# NCKH_cap_truong_Thien.net
KiCad netlist of a schematic drawn in Altium Designer
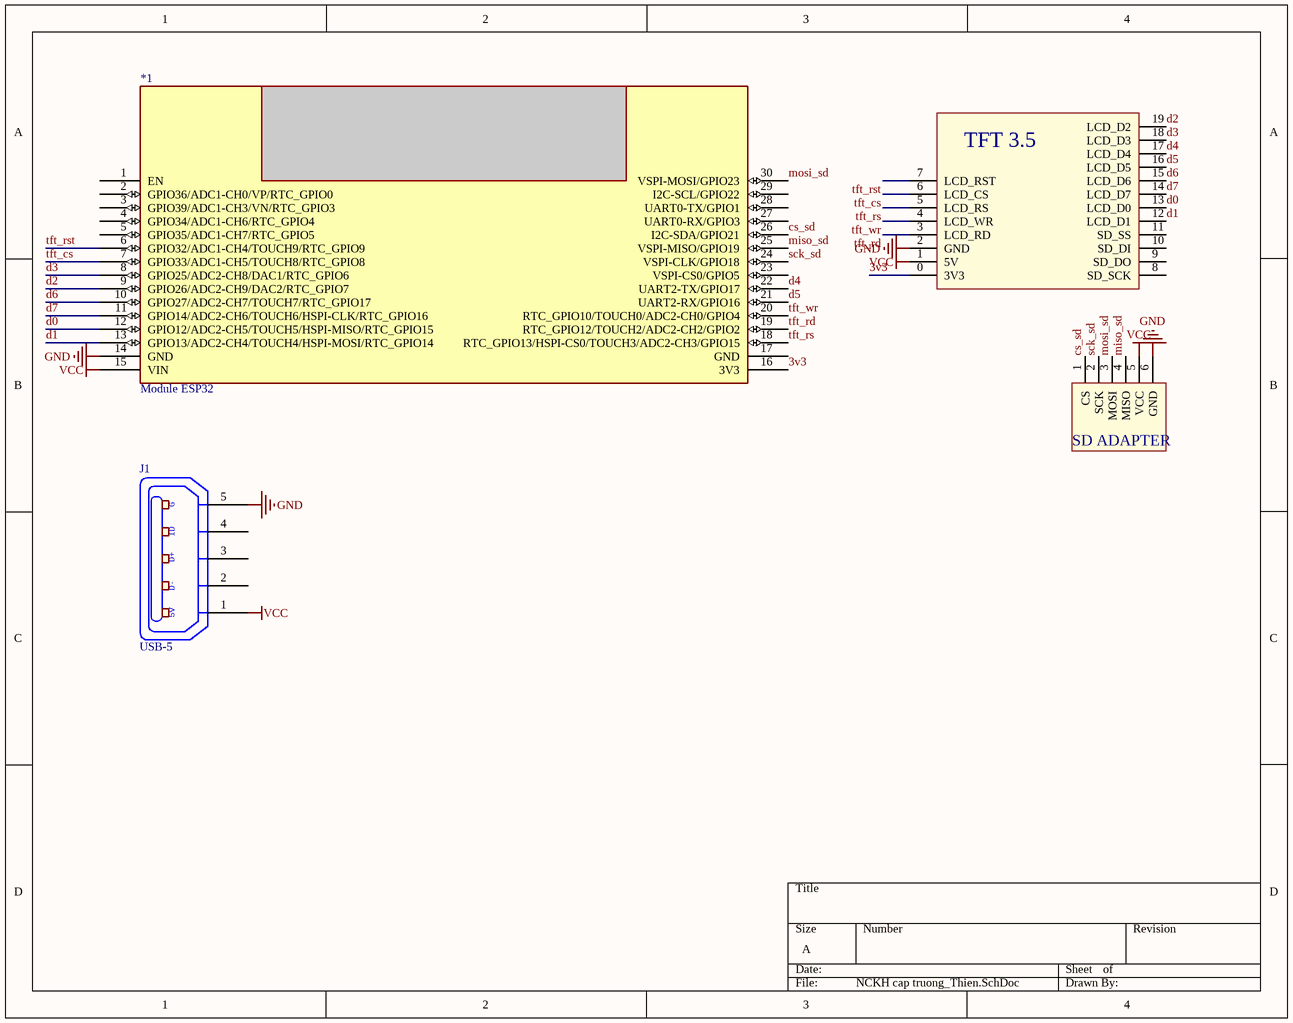
[diagram p0: NCKH cap truong_Thien.SchDoc]

(export (version "E")
  (design (tool "Eeschema 10.0.6"))
  (components
    (comp (ref "*1")
      (value "Module ESP32")
      (footprint "Module ESP32")
      (libsource (lib "Lib_NTD") (part "Module ESP32"))
    )
    (comp (ref "*2")
      (value "LCD TFT 3.5 Shield")
      (footprint "LCD TFT 3.5 Shield")
      (libsource (lib "Lib_NTD") (part "LCD TFT 3.5 Shield"))
    )
    (comp (ref "*3")
      (value "Module MicroSD Adapter")
      (footprint "Module MicroSD Adapter")
      (libsource (lib "Lib_NTD") (part "Module MicroSD Adapter"))
    )
    (comp (ref "J1")
      (value "USB-5")
      (footprint "USB-M1")
      (fields
        (field (name "MANUFACTURER") "FCI")
        (field (name "MANUFACTURER PART NUMBER") "10118193-0001LF")
        (field (name ".CREATOR") "MM")
        (field (name ".CHECKED PCB") "RF")
        (field (name ".CHECKED SCH") "MM")
      )
      (libsource (lib "LIBRARY") (part "USB-5"))
    )
  )
  (nets
    (net (code "1") (name "/3v3") (class "Default")
      (node (ref "*1") (pin "16") (pinfunction "3V3_16") (pintype "power_in"))
      (node (ref "*2") (pin "0") (pinfunction "3V3_0") (pintype "passive"))
    )
    (net (code "2") (name "/cs_sd") (class "Default")
      (node (ref "*1") (pin "26") (pinfunction "I2C-SDA/GPIO21_26") (pintype "bidirectional"))
      (node (ref "*3") (pin "1") (pinfunction "CS_1") (pintype "passive"))
    )
    (net (code "3") (name "/d0") (class "Default")
      (node (ref "*1") (pin "12") (pinfunction "GPIO12/ADC2-CH5/TOUCH5/HSPI-MISO/RTC_GPIO15_12") (pintype "bidirectional"))
      (node (ref "*2") (pin "13") (pinfunction "LCD_D0_13") (pintype "passive"))
    )
    (net (code "4") (name "/d1") (class "Default")
      (node (ref "*1") (pin "13") (pinfunction "GPIO13/ADC2-CH4/TOUCH4/HSPI-MOSI/RTC_GPIO14_13") (pintype "bidirectional"))
      (node (ref "*2") (pin "12") (pinfunction "LCD_D1_12") (pintype "passive"))
    )
    (net (code "5") (name "/d2") (class "Default")
      (node (ref "*1") (pin "9") (pinfunction "GPIO26/ADC2-CH9/DAC2/RTC_GPIO7_9") (pintype "bidirectional"))
      (node (ref "*2") (pin "19") (pinfunction "LCD_D2_19") (pintype "passive"))
    )
    (net (code "6") (name "/d3") (class "Default")
      (node (ref "*1") (pin "8") (pinfunction "GPIO25/ADC2-CH8/DAC1/RTC_GPIO6_8") (pintype "bidirectional"))
      (node (ref "*2") (pin "18") (pinfunction "LCD_D3_18") (pintype "passive"))
    )
    (net (code "7") (name "/d4") (class "Default")
      (node (ref "*1") (pin "22") (pinfunction "UART2-TX/GPIO17_22") (pintype "bidirectional"))
      (node (ref "*2") (pin "17") (pinfunction "LCD_D4_17") (pintype "passive"))
    )
    (net (code "8") (name "/d5") (class "Default")
      (node (ref "*1") (pin "21") (pinfunction "UART2-RX/GPIO16_21") (pintype "bidirectional"))
      (node (ref "*2") (pin "16") (pinfunction "LCD_D5_16") (pintype "passive"))
    )
    (net (code "9") (name "/d6") (class "Default")
      (node (ref "*1") (pin "10") (pinfunction "GPIO27/ADC2-CH7/TOUCH7/RTC_GPIO17_10") (pintype "bidirectional"))
      (node (ref "*2") (pin "15") (pinfunction "LCD_D6_15") (pintype "passive"))
    )
    (net (code "10") (name "/d7") (class "Default")
      (node (ref "*1") (pin "11") (pinfunction "GPIO14/ADC2-CH6/TOUCH6/HSPI-CLK/RTC_GPIO16_11") (pintype "bidirectional"))
      (node (ref "*2") (pin "14") (pinfunction "LCD_D7_14") (pintype "passive"))
    )
    (net (code "11") (name "/miso_sd") (class "Default")
      (node (ref "*1") (pin "25") (pinfunction "VSPI-MISO/GPIO19_25") (pintype "bidirectional"))
      (node (ref "*3") (pin "4") (pinfunction "MISO_4") (pintype "passive"))
    )
    (net (code "12") (name "/mosi_sd") (class "Default")
      (node (ref "*1") (pin "30") (pinfunction "VSPI-MOSI/GPIO23_30") (pintype "bidirectional"))
      (node (ref "*3") (pin "3") (pinfunction "MOSI_3") (pintype "passive"))
    )
    (net (code "13") (name "/sck_sd") (class "Default")
      (node (ref "*1") (pin "24") (pinfunction "VSPI-CLK/GPIO18_24") (pintype "bidirectional"))
      (node (ref "*3") (pin "2") (pinfunction "SCK_2") (pintype "passive"))
    )
    (net (code "14") (name "/tft_cs") (class "Default")
      (node (ref "*1") (pin "7") (pinfunction "GPIO33/ADC1-CH5/TOUCH8/RTC_GPIO8_7") (pintype "bidirectional"))
      (node (ref "*2") (pin "6") (pinfunction "LCD_CS_6") (pintype "passive"))
    )
    (net (code "15") (name "/tft_rd") (class "Default")
      (node (ref "*1") (pin "19") (pinfunction "RTC_GPIO12/TOUCH2/ADC2-CH2/GPIO2_19") (pintype "bidirectional"))
      (node (ref "*2") (pin "3") (pinfunction "LCD_RD_3") (pintype "passive"))
    )
    (net (code "16") (name "/tft_rs") (class "Default")
      (node (ref "*1") (pin "18") (pinfunction "RTC_GPIO13/HSPI-CS0/TOUCH3/ADC2-CH3/GPIO15_18") (pintype "bidirectional"))
      (node (ref "*2") (pin "5") (pinfunction "LCD_RS_5") (pintype "passive"))
    )
    (net (code "17") (name "/tft_rst") (class "Default")
      (node (ref "*1") (pin "6") (pinfunction "GPIO32/ADC1-CH4/TOUCH9/RTC_GPIO9_6") (pintype "bidirectional"))
      (node (ref "*2") (pin "7") (pinfunction "LCD_RST_7") (pintype "passive"))
    )
    (net (code "18") (name "/tft_wr") (class "Default")
      (node (ref "*1") (pin "20") (pinfunction "RTC_GPIO10/TOUCH0/ADC2-CH0/GPIO4_20") (pintype "bidirectional"))
      (node (ref "*2") (pin "4") (pinfunction "LCD_WR_4") (pintype "passive"))
    )
    (net (code "19") (name "GND") (class "Default")
      (node (ref "*1") (pin "14") (pinfunction "GND_14") (pintype "power_in"))
      (node (ref "*2") (pin "2") (pinfunction "GND_2") (pintype "passive"))
      (node (ref "*3") (pin "6") (pinfunction "GND_6") (pintype "passive"))
      (node (ref "J1") (pin "5") (pinfunction "P5_5") (pintype "passive"))
    )
    (net (code "20") (name "VCC") (class "Default")
      (node (ref "*1") (pin "15") (pinfunction "VIN_15") (pintype "power_in"))
      (node (ref "*2") (pin "1") (pinfunction "5V_1") (pintype "passive"))
      (node (ref "*3") (pin "5") (pinfunction "VCC_5") (pintype "passive"))
      (node (ref "J1") (pin "1") (pinfunction "P1_1") (pintype "passive"))
    )
    (net (code "21") (name "unconnected-(*1-EN-Pad1)") (class "Default")
      (node (ref "*1") (pin "1") (pinfunction "EN_1") (pintype "passive"))
    )
    (net (code "22") (name "unconnected-(*1-GND-Pad17)") (class "Default")
      (node (ref "*1") (pin "17") (pinfunction "GND_17") (pintype "power_in"))
    )
    (net (code "23") (name "unconnected-(*1-GPIO34{slash}ADC1-CH6{slash}RTC_GPIO4-Pad4)") (class "Default")
      (node (ref "*1") (pin "4") (pinfunction "GPIO34/ADC1-CH6/RTC_GPIO4_4") (pintype "bidirectional"))
    )
    (net (code "24") (name "unconnected-(*1-GPIO35{slash}ADC1-CH7{slash}RTC_GPIO5-Pad5)") (class "Default")
      (node (ref "*1") (pin "5") (pinfunction "GPIO35/ADC1-CH7/RTC_GPIO5_5") (pintype "bidirectional"))
    )
    (net (code "25") (name "unconnected-(*1-GPIO36{slash}ADC1-CH0{slash}VP{slash}RTC_GPIO0-Pad2)") (class "Default")
      (node (ref "*1") (pin "2") (pinfunction "GPIO36/ADC1-CH0/VP/RTC_GPIO0_2") (pintype "bidirectional"))
    )
    (net (code "26") (name "unconnected-(*1-GPIO39{slash}ADC1-CH3{slash}VN{slash}RTC_GPIO3-Pad3)") (class "Default")
      (node (ref "*1") (pin "3") (pinfunction "GPIO39/ADC1-CH3/VN/RTC_GPIO3_3") (pintype "bidirectional"))
    )
    (net (code "27") (name "unconnected-(*1-I2C-SCL{slash}GPIO22-Pad29)") (class "Default")
      (node (ref "*1") (pin "29") (pinfunction "I2C-SCL/GPIO22_29") (pintype "bidirectional"))
    )
    (net (code "28") (name "unconnected-(*1-UART0-RX{slash}GPIO3-Pad27)") (class "Default")
      (node (ref "*1") (pin "27") (pinfunction "UART0-RX/GPIO3_27") (pintype "bidirectional"))
    )
    (net (code "29") (name "unconnected-(*1-UART0-TX{slash}GPIO1-Pad28)") (class "Default")
      (node (ref "*1") (pin "28") (pinfunction "UART0-TX/GPIO1_28") (pintype "bidirectional"))
    )
    (net (code "30") (name "unconnected-(*1-VSPI-CS0{slash}GPIO5-Pad23)") (class "Default")
      (node (ref "*1") (pin "23") (pinfunction "VSPI-CS0/GPIO5_23") (pintype "bidirectional"))
    )
    (net (code "31") (name "unconnected-(*2-SD_DI-Pad10)") (class "Default")
      (node (ref "*2") (pin "10") (pinfunction "SD_DI_10") (pintype "passive"))
    )
    (net (code "32") (name "unconnected-(*2-SD_DO-Pad9)") (class "Default")
      (node (ref "*2") (pin "9") (pinfunction "SD_DO_9") (pintype "passive"))
    )
    (net (code "33") (name "unconnected-(*2-SD_SCK-Pad8)") (class "Default")
      (node (ref "*2") (pin "8") (pinfunction "SD_SCK_8") (pintype "passive"))
    )
    (net (code "34") (name "unconnected-(*2-SD_SS-Pad11)") (class "Default")
      (node (ref "*2") (pin "11") (pinfunction "SD_SS_11") (pintype "passive"))
    )
    (net (code "35") (name "unconnected-(J1-P2-Pad2)") (class "Default")
      (node (ref "J1") (pin "2") (pinfunction "P2_2") (pintype "passive"))
    )
    (net (code "36") (name "unconnected-(J1-P3-Pad3)") (class "Default")
      (node (ref "J1") (pin "3") (pinfunction "P3_3") (pintype "passive"))
    )
    (net (code "37") (name "unconnected-(J1-P4-Pad4)") (class "Default")
      (node (ref "J1") (pin "4") (pinfunction "P4_4") (pintype "passive"))
    )
  )
)
